# Adafruit_2_13in_Tri-Color_eInk_Display.net
KiCad netlist of a schematic drawn in EAGLE
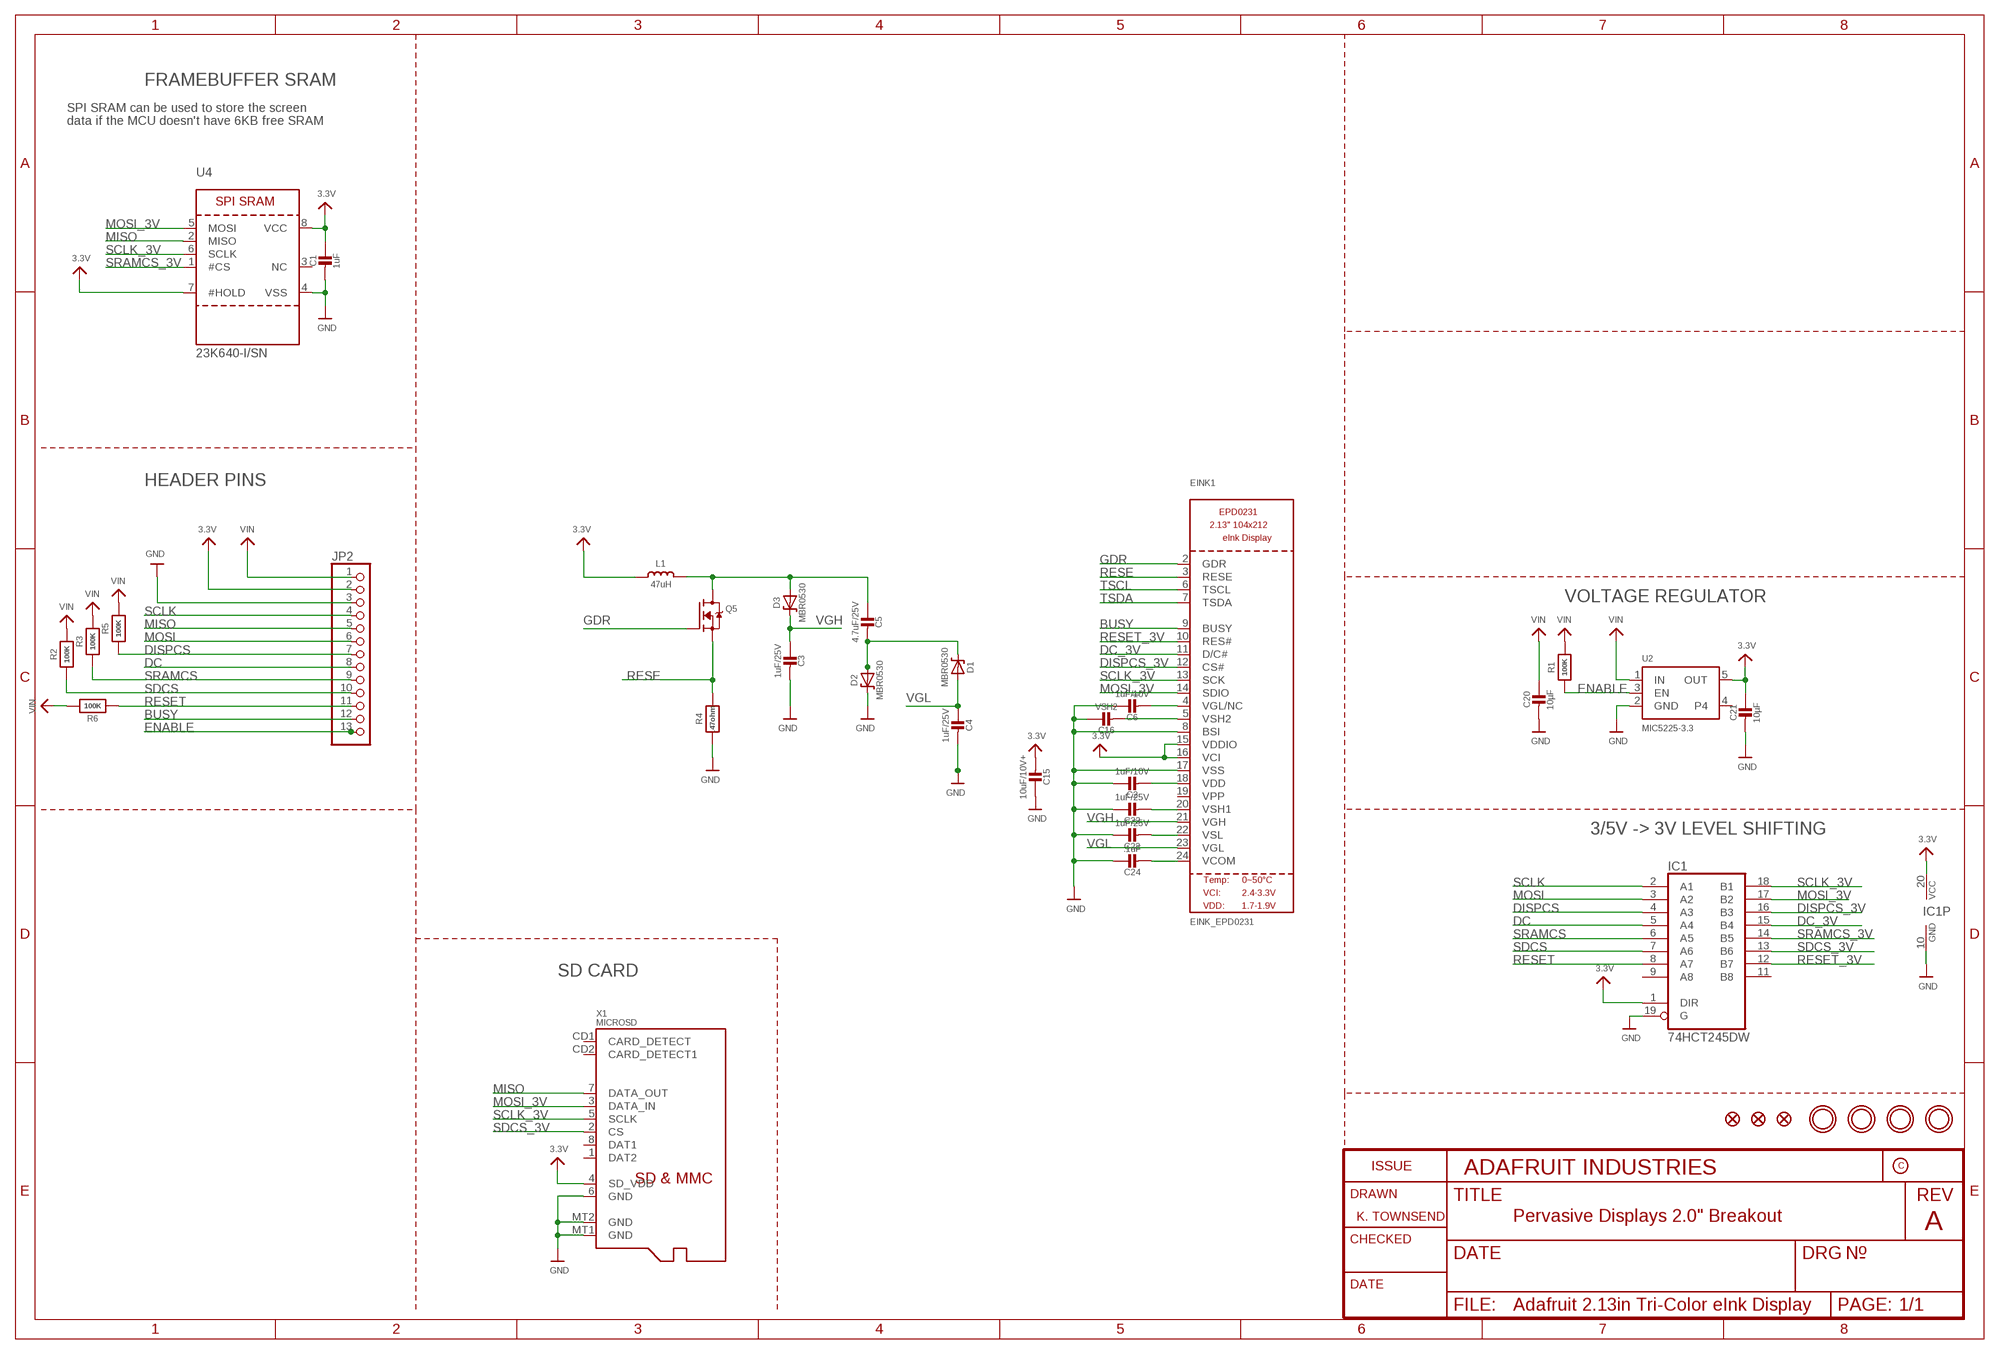
[diagram p0: schematic, sheet 1]

(export (version "E")
  (design (tool "Eeschema 10.0.6"))
  (components
    (comp (ref "C1")
      (value "1uF")
      (footprint "eagle-import:0805_10MGAP")
      (libsource (lib "eagle-import") (part "CAP_CERAMIC0805_10MGAP"))
    )
    (comp (ref "C2")
      (value "1uF/10V")
      (footprint "eagle-import:0805-NO")
      (libsource (lib "eagle-import") (part "CAP_CERAMIC0805-NOOUTLINE"))
    )
    (comp (ref "C3")
      (value "1uF/25V")
      (footprint "eagle-import:0805-NO")
      (libsource (lib "eagle-import") (part "CAP_CERAMIC0805-NOOUTLINE"))
    )
    (comp (ref "C4")
      (value "1uF/25V")
      (footprint "eagle-import:0805-NO")
      (libsource (lib "eagle-import") (part "CAP_CERAMIC0805-NOOUTLINE"))
    )
    (comp (ref "C5")
      (value "4.7uF/25V")
      (footprint "eagle-import:0805-NO")
      (libsource (lib "eagle-import") (part "CAP_CERAMIC0805-NOOUTLINE"))
    )
    (comp (ref "C6")
      (value "1uF/10V")
      (footprint "eagle-import:0805-NO")
      (libsource (lib "eagle-import") (part "CAP_CERAMIC0805-NOOUTLINE"))
    )
    (comp (ref "C15")
      (value "10uF/10V+")
      (footprint "eagle-import:0805-NO")
      (libsource (lib "eagle-import") (part "CAP_CERAMIC0805-NOOUTLINE"))
    )
    (comp (ref "C16")
      (value "VSH2")
      (footprint "eagle-import:0805-NO")
      (libsource (lib "eagle-import") (part "CAP_CERAMIC0805-NOOUTLINE"))
    )
    (comp (ref "C20")
      (value "10µF")
      (footprint "eagle-import:0805-NO")
      (libsource (lib "eagle-import") (part "CAP_CERAMIC0805-NOOUTLINE"))
    )
    (comp (ref "C21")
      (value "10µF")
      (footprint "eagle-import:0805-NO")
      (libsource (lib "eagle-import") (part "CAP_CERAMIC0805-NOOUTLINE"))
    )
    (comp (ref "C22")
      (value "1uF/25V")
      (footprint "eagle-import:0805-NO")
      (libsource (lib "eagle-import") (part "CAP_CERAMIC0805-NOOUTLINE"))
    )
    (comp (ref "C23")
      (value "1uF/25V")
      (footprint "eagle-import:0805-NO")
      (libsource (lib "eagle-import") (part "CAP_CERAMIC0805-NOOUTLINE"))
    )
    (comp (ref "C24")
      (value ".1uF")
      (footprint "eagle-import:0805-NO")
      (libsource (lib "eagle-import") (part "CAP_CERAMIC0805-NOOUTLINE"))
    )
    (comp (ref "D1")
      (value "MBR0530")
      (footprint "eagle-import:SOD-123")
      (libsource (lib "eagle-import") (part "DIODE-SCHOTTKYSOD-123"))
    )
    (comp (ref "D2")
      (value "MBR0530")
      (footprint "eagle-import:SOD-123")
      (libsource (lib "eagle-import") (part "DIODE-SCHOTTKYSOD-123"))
    )
    (comp (ref "D3")
      (value "MBR0530")
      (footprint "eagle-import:SOD-123")
      (libsource (lib "eagle-import") (part "DIODE-SCHOTTKYSOD-123"))
    )
    (comp (ref "EINK1")
      (value "EINK_EPD0231")
      (footprint "eagle-import:EINK_213IN_104X212")
      (libsource (lib "eagle-import") (part "EINK_EPD0231"))
    )
    (comp (ref "FID1")
      (value "FIDUCIAL_1MM")
      (footprint "eagle-import:FIDUCIAL_1MM")
      (libsource (lib "eagle-import") (part "FIDUCIAL_1MM"))
    )
    (comp (ref "FID2")
      (value "FIDUCIAL_1MM")
      (footprint "eagle-import:FIDUCIAL_1MM")
      (libsource (lib "eagle-import") (part "FIDUCIAL_1MM"))
    )
    (comp (ref "FID3")
      (value "FIDUCIAL_1MM")
      (footprint "eagle-import:FIDUCIAL_1MM")
      (libsource (lib "eagle-import") (part "FIDUCIAL_1MM"))
    )
    (comp (ref "IC1")
      (value "74HCT245DW")
      (footprint "eagle-import:SO20W")
      (libsource (lib "eagle-import") (part "74245DWHCT"))
    )
    (comp (ref "JP2")
      (value "HEADER-1X13")
      (footprint "eagle-import:1X13_ROUND_70")
      (libsource (lib "eagle-import") (part "HEADER-1X13"))
    )
    (comp (ref "L1")
      (value "47uH")
      (footprint "eagle-import:INDUCTOR_4X4MM_NR401")
      (libsource (lib "eagle-import") (part "INDUCTORNR401"))
    )
    (comp (ref "Q5")
      (value "IRLML0100")
      (footprint "eagle-import:SOT23-3")
      (libsource (lib "eagle-import") (part "IRLML2060TRPBF"))
    )
    (comp (ref "R1")
      (value "100K")
      (footprint "eagle-import:0805-NO")
      (libsource (lib "eagle-import") (part "RESISTOR0805_NOOUTLINE"))
    )
    (comp (ref "R2")
      (value "100K")
      (footprint "eagle-import:0805-NO")
      (libsource (lib "eagle-import") (part "RESISTOR0805_NOOUTLINE"))
    )
    (comp (ref "R3")
      (value "100K")
      (footprint "eagle-import:0805-NO")
      (libsource (lib "eagle-import") (part "RESISTOR0805_NOOUTLINE"))
    )
    (comp (ref "R4")
      (value ".47ohm")
      (footprint "eagle-import:0805_10MGAP")
      (libsource (lib "eagle-import") (part "RESISTOR0805_10MGAP"))
    )
    (comp (ref "R5")
      (value "100K")
      (footprint "eagle-import:0805-NO")
      (libsource (lib "eagle-import") (part "RESISTOR0805_NOOUTLINE"))
    )
    (comp (ref "R6")
      (value "100K")
      (footprint "eagle-import:0805-NO")
      (libsource (lib "eagle-import") (part "RESISTOR0805_NOOUTLINE"))
    )
    (comp (ref "U$3")
      (value "MOUNTINGHOLE2.5")
      (footprint "eagle-import:MOUNTINGHOLE_2.5_PLATED")
      (libsource (lib "eagle-import") (part "MOUNTINGHOLE2.5"))
    )
    (comp (ref "U$4")
      (value "MOUNTINGHOLE2.5")
      (footprint "eagle-import:MOUNTINGHOLE_2.5_PLATED")
      (libsource (lib "eagle-import") (part "MOUNTINGHOLE2.5"))
    )
    (comp (ref "U$5")
      (value "MOUNTINGHOLE2.5")
      (footprint "eagle-import:MOUNTINGHOLE_2.5_PLATED")
      (libsource (lib "eagle-import") (part "MOUNTINGHOLE2.5"))
    )
    (comp (ref "U$6")
      (value "MOUNTINGHOLE2.5")
      (footprint "eagle-import:MOUNTINGHOLE_2.5_PLATED")
      (libsource (lib "eagle-import") (part "MOUNTINGHOLE2.5"))
    )
    (comp (ref "U2")
      (value "MIC5225-3.3")
      (footprint "eagle-import:SOT23-5")
      (libsource (lib "eagle-import") (part "VREG_SOT23-5"))
    )
    (comp (ref "U4")
      (value "23K640-I/SN")
      (footprint "eagle-import:SOIC8_150MIL")
      (libsource (lib "eagle-import") (part "SRAM_SPI_SOIC8"))
    )
    (comp (ref "X1")
      (value "MICROSD")
      (footprint "eagle-import:MICROSD")
      (libsource (lib "eagle-import") (part "MICROSD"))
    )
  )
  (nets
    (net (code "1") (name "/BUSY") (class "Default")
      (node (ref "EINK1") (pin "9") (pinfunction "BUSY_9") (pintype "output"))
      (node (ref "JP2") (pin "12") (pinfunction "12_12") (pintype "passive"))
    )
    (net (code "2") (name "/DC") (class "Default")
      (node (ref "IC1") (pin "5") (pinfunction "A4_5") (pintype "bidirectional"))
      (node (ref "JP2") (pin "8") (pinfunction "8_8") (pintype "passive"))
    )
    (net (code "3") (name "/DC_3V") (class "Default")
      (node (ref "EINK1") (pin "11") (pinfunction "D/C#_11") (pintype "input"))
      (node (ref "IC1") (pin "15") (pinfunction "B4_15") (pintype "bidirectional"))
    )
    (net (code "4") (name "/DISPCS") (class "Default")
      (node (ref "IC1") (pin "4") (pinfunction "A3_4") (pintype "bidirectional"))
      (node (ref "JP2") (pin "7") (pinfunction "7_7") (pintype "passive"))
      (node (ref "R5") (pin "1") (pinfunction "1_1") (pintype "passive"))
    )
    (net (code "5") (name "/DISPCS_3V") (class "Default")
      (node (ref "EINK1") (pin "12") (pinfunction "CS#_12") (pintype "input"))
      (node (ref "IC1") (pin "16") (pinfunction "B3_16") (pintype "bidirectional"))
    )
    (net (code "6") (name "/ENABLE") (class "Default")
      (node (ref "JP2") (pin "13") (pinfunction "13_13") (pintype "passive"))
      (node (ref "R1") (pin "1") (pinfunction "1_1") (pintype "passive"))
      (node (ref "U2") (pin "3") (pinfunction "EN_3") (pintype "input"))
    )
    (net (code "7") (name "/GDR") (class "Default")
      (node (ref "EINK1") (pin "2") (pinfunction "GDR_2") (pintype "output"))
      (node (ref "Q5") (pin "1") (pinfunction "G_1") (pintype "bidirectional"))
    )
    (net (code "8") (name "/MISO") (class "Default")
      (node (ref "JP2") (pin "5") (pinfunction "5_5") (pintype "passive"))
      (node (ref "U4") (pin "2") (pinfunction "MISO_2") (pintype "output"))
      (node (ref "X1") (pin "7") (pinfunction "DATA_OUT_7") (pintype "output"))
    )
    (net (code "9") (name "/MOSI") (class "Default")
      (node (ref "IC1") (pin "3") (pinfunction "A2_3") (pintype "bidirectional"))
      (node (ref "JP2") (pin "6") (pinfunction "6_6") (pintype "passive"))
    )
    (net (code "10") (name "/MOSI_3V") (class "Default")
      (node (ref "EINK1") (pin "14") (pinfunction "SDIO_14") (pintype "bidirectional"))
      (node (ref "IC1") (pin "17") (pinfunction "B2_17") (pintype "bidirectional"))
      (node (ref "U4") (pin "5") (pinfunction "MOSI_5") (pintype "input"))
      (node (ref "X1") (pin "3") (pinfunction "DATA_IN_3") (pintype "input"))
    )
    (net (code "11") (name "/RESE") (class "Default")
      (node (ref "EINK1") (pin "3") (pinfunction "RESE_3") (pintype "input"))
      (node (ref "Q5") (pin "2") (pinfunction "S_2") (pintype "bidirectional"))
      (node (ref "R4") (pin "1") (pinfunction "1_1") (pintype "passive"))
    )
    (net (code "12") (name "/RESET") (class "Default")
      (node (ref "IC1") (pin "8") (pinfunction "A7_8") (pintype "bidirectional"))
      (node (ref "JP2") (pin "11") (pinfunction "11_11") (pintype "passive"))
      (node (ref "R6") (pin "1") (pinfunction "1_1") (pintype "passive"))
    )
    (net (code "13") (name "/RESET_3V") (class "Default")
      (node (ref "EINK1") (pin "10") (pinfunction "RES#_10") (pintype "input"))
      (node (ref "IC1") (pin "12") (pinfunction "B7_12") (pintype "bidirectional"))
    )
    (net (code "14") (name "/SCLK") (class "Default")
      (node (ref "IC1") (pin "2") (pinfunction "A1_2") (pintype "bidirectional"))
      (node (ref "JP2") (pin "4") (pinfunction "4_4") (pintype "passive"))
    )
    (net (code "15") (name "/SCLK_3V") (class "Default")
      (node (ref "EINK1") (pin "13") (pinfunction "SCK_13") (pintype "bidirectional"))
      (node (ref "IC1") (pin "18") (pinfunction "B1_18") (pintype "bidirectional"))
      (node (ref "U4") (pin "6") (pinfunction "SCLK_6") (pintype "input"))
      (node (ref "X1") (pin "5") (pinfunction "SCLK_5") (pintype "input"))
    )
    (net (code "16") (name "/SDCS") (class "Default")
      (node (ref "IC1") (pin "7") (pinfunction "A6_7") (pintype "bidirectional"))
      (node (ref "JP2") (pin "10") (pinfunction "10_10") (pintype "passive"))
      (node (ref "R2") (pin "1") (pinfunction "1_1") (pintype "passive"))
    )
    (net (code "17") (name "/SDCS_3V") (class "Default")
      (node (ref "IC1") (pin "13") (pinfunction "B6_13") (pintype "bidirectional"))
      (node (ref "X1") (pin "2") (pinfunction "CS_2") (pintype "input"))
    )
    (net (code "18") (name "/SRAMCS") (class "Default")
      (node (ref "IC1") (pin "6") (pinfunction "A5_6") (pintype "bidirectional"))
      (node (ref "JP2") (pin "9") (pinfunction "9_9") (pintype "passive"))
      (node (ref "R3") (pin "1") (pinfunction "1_1") (pintype "passive"))
    )
    (net (code "19") (name "/SRAMCS_3V") (class "Default")
      (node (ref "IC1") (pin "14") (pinfunction "B5_14") (pintype "bidirectional"))
      (node (ref "U4") (pin "1") (pinfunction "#CS_1") (pintype "input"))
    )
    (net (code "20") (name "/TSCL") (class "Default")
      (node (ref "EINK1") (pin "6") (pinfunction "TSCL_6") (pintype "output"))
    )
    (net (code "21") (name "/TSDA") (class "Default")
      (node (ref "EINK1") (pin "7") (pinfunction "TSDA_7") (pintype "bidirectional"))
    )
    (net (code "22") (name "/VGH") (class "Default")
      (node (ref "C3") (pin "1") (pinfunction "1_1") (pintype "passive"))
      (node (ref "D3") (pin "C") (pinfunction "C_C") (pintype "passive"))
      (node (ref "EINK1") (pin "21") (pinfunction "VGH_21") (pintype "passive"))
    )
    (net (code "23") (name "/VGL") (class "Default")
      (node (ref "C4") (pin "1") (pinfunction "1_1") (pintype "passive"))
      (node (ref "D1") (pin "A") (pinfunction "A_A") (pintype "passive"))
      (node (ref "EINK1") (pin "23") (pinfunction "VGL_23") (pintype "passive"))
    )
    (net (code "24") (name "3.3V") (class "Default")
      (node (ref "C1") (pin "1") (pinfunction "1_1") (pintype "passive"))
      (node (ref "C15") (pin "2") (pinfunction "2_2") (pintype "passive"))
      (node (ref "C21") (pin "1") (pinfunction "1_1") (pintype "passive"))
      (node (ref "EINK1") (pin "15") (pinfunction "VDDIO_15") (pintype "power_in"))
      (node (ref "EINK1") (pin "16") (pinfunction "VCI_16") (pintype "power_in"))
      (node (ref "IC1") (pin "1") (pinfunction "DIR_1") (pintype "input"))
      (node (ref "IC1") (pin "20") (pinfunction "VCC_20") (pintype "power_in"))
      (node (ref "JP2") (pin "2") (pinfunction "2_2") (pintype "passive"))
      (node (ref "L1") (pin "P$2") (pinfunction "2_P$2") (pintype "passive"))
      (node (ref "U2") (pin "5") (pinfunction "OUT_5") (pintype "power_in"))
      (node (ref "U4") (pin "7") (pinfunction "#HOLD_7") (pintype "input"))
      (node (ref "U4") (pin "8") (pinfunction "VCC_8") (pintype "power_in"))
      (node (ref "X1") (pin "4") (pinfunction "SD_VDD_4") (pintype "power_in"))
    )
    (net (code "25") (name "GND") (class "Default")
      (node (ref "C1") (pin "2") (pinfunction "2_2") (pintype "passive"))
      (node (ref "C15") (pin "1") (pinfunction "1_1") (pintype "passive"))
      (node (ref "C16") (pin "1") (pinfunction "1_1") (pintype "passive"))
      (node (ref "C2") (pin "1") (pinfunction "1_1") (pintype "passive"))
      (node (ref "C20") (pin "2") (pinfunction "2_2") (pintype "passive"))
      (node (ref "C21") (pin "2") (pinfunction "2_2") (pintype "passive"))
      (node (ref "C22") (pin "1") (pinfunction "1_1") (pintype "passive"))
      (node (ref "C23") (pin "1") (pinfunction "1_1") (pintype "passive"))
      (node (ref "C24") (pin "1") (pinfunction "1_1") (pintype "passive"))
      (node (ref "C3") (pin "2") (pinfunction "2_2") (pintype "passive"))
      (node (ref "C4") (pin "2") (pinfunction "2_2") (pintype "passive"))
      (node (ref "C6") (pin "1") (pinfunction "1_1") (pintype "passive"))
      (node (ref "D2") (pin "C") (pinfunction "C_C") (pintype "passive"))
      (node (ref "EINK1") (pin "17") (pinfunction "VSS_17") (pintype "power_in"))
      (node (ref "EINK1") (pin "8") (pinfunction "BSI_8") (pintype "input"))
      (node (ref "IC1") (pin "10") (pinfunction "GND_10") (pintype "power_in"))
      (node (ref "IC1") (pin "19") (pinfunction "G_19") (pintype "input"))
      (node (ref "JP2") (pin "3") (pinfunction "3_3") (pintype "passive"))
      (node (ref "R4") (pin "2") (pinfunction "2_2") (pintype "passive"))
      (node (ref "U2") (pin "2") (pinfunction "GND_2") (pintype "power_in"))
      (node (ref "U4") (pin "4") (pinfunction "VSS_4") (pintype "power_in"))
      (node (ref "X1") (pin "6") (pinfunction "GND_6") (pintype "power_in"))
      (node (ref "X1") (pin "MT1") (pinfunction "GND_MT1") (pintype "power_in"))
      (node (ref "X1") (pin "MT2") (pinfunction "GND_MT2") (pintype "power_in"))
    )
    (net (code "26") (name "Net-(C5-Pad2)") (class "Default")
      (node (ref "C5") (pin "2") (pinfunction "2_2") (pintype "passive"))
      (node (ref "D1") (pin "C") (pinfunction "C_C") (pintype "passive"))
      (node (ref "D2") (pin "A") (pinfunction "A_A") (pintype "passive"))
    )
    (net (code "27") (name "Net-(EINK1-VCOM)") (class "Default")
      (node (ref "C24") (pin "2") (pinfunction "2_2") (pintype "passive"))
      (node (ref "EINK1") (pin "24") (pinfunction "VCOM_24") (pintype "passive"))
    )
    (net (code "28") (name "Net-(EINK1-VDD)") (class "Default")
      (node (ref "C2") (pin "2") (pinfunction "2_2") (pintype "passive"))
      (node (ref "EINK1") (pin "18") (pinfunction "VDD_18") (pintype "passive"))
    )
    (net (code "29") (name "Net-(EINK1-VGL{slash}NC)") (class "Default")
      (node (ref "C6") (pin "2") (pinfunction "2_2") (pintype "passive"))
      (node (ref "EINK1") (pin "4") (pinfunction "VGL/NC_4") (pintype "bidirectional"))
    )
    (net (code "30") (name "Net-(EINK1-VSH1)") (class "Default")
      (node (ref "C22") (pin "2") (pinfunction "2_2") (pintype "passive"))
      (node (ref "EINK1") (pin "20") (pinfunction "VSH1_20") (pintype "passive"))
    )
    (net (code "31") (name "Net-(EINK1-VSH2)") (class "Default")
      (node (ref "C16") (pin "2") (pinfunction "2_2") (pintype "passive"))
      (node (ref "EINK1") (pin "5") (pinfunction "VSH2_5") (pintype "passive"))
    )
    (net (code "32") (name "Net-(EINK1-VSL)") (class "Default")
      (node (ref "C23") (pin "2") (pinfunction "2_2") (pintype "passive"))
      (node (ref "EINK1") (pin "22") (pinfunction "VSL_22") (pintype "passive"))
    )
    (net (code "33") (name "Net-(L1-1)") (class "Default")
      (node (ref "C5") (pin "1") (pinfunction "1_1") (pintype "passive"))
      (node (ref "D3") (pin "A") (pinfunction "A_A") (pintype "passive"))
      (node (ref "L1") (pin "P$1") (pinfunction "1_P$1") (pintype "passive"))
      (node (ref "Q5") (pin "3") (pinfunction "D_3") (pintype "bidirectional"))
    )
    (net (code "34") (name "VIN") (class "Default")
      (node (ref "C20") (pin "1") (pinfunction "1_1") (pintype "passive"))
      (node (ref "JP2") (pin "1") (pinfunction "1_1") (pintype "passive"))
      (node (ref "R1") (pin "2") (pinfunction "2_2") (pintype "passive"))
      (node (ref "R2") (pin "2") (pinfunction "2_2") (pintype "passive"))
      (node (ref "R3") (pin "2") (pinfunction "2_2") (pintype "passive"))
      (node (ref "R5") (pin "2") (pinfunction "2_2") (pintype "passive"))
      (node (ref "R6") (pin "2") (pinfunction "2_2") (pintype "passive"))
      (node (ref "U2") (pin "1") (pinfunction "IN_1") (pintype "power_in"))
    )
    (net (code "35") (name "unconnected-(EINK1-VPP-Pad19)") (class "Default")
      (node (ref "EINK1") (pin "19") (pinfunction "VPP_19") (pintype "passive"))
    )
    (net (code "36") (name "unconnected-(IC1A-A8-Pad9)") (class "Default")
      (node (ref "IC1") (pin "9") (pinfunction "A8_9") (pintype "bidirectional"))
    )
    (net (code "37") (name "unconnected-(IC1A-B8-Pad11)") (class "Default")
      (node (ref "IC1") (pin "11") (pinfunction "B8_11") (pintype "bidirectional"))
    )
    (net (code "38") (name "unconnected-(U2-P4-Pad4)") (class "Default")
      (node (ref "U2") (pin "4") (pinfunction "P4_4") (pintype "bidirectional"))
    )
    (net (code "39") (name "unconnected-(U4-NC-Pad3)") (class "Default")
      (node (ref "U4") (pin "3") (pinfunction "NC_3") (pintype "no_connect"))
    )
    (net (code "40") (name "unconnected-(X1-CARD_DETECT-PadCD1)") (class "Default")
      (node (ref "X1") (pin "CD1") (pinfunction "CARD_DETECT_CD1") (pintype "passive"))
    )
    (net (code "41") (name "unconnected-(X1-CARD_DETECT1-PadCD2)") (class "Default")
      (node (ref "X1") (pin "CD2") (pinfunction "CARD_DETECT1_CD2") (pintype "passive"))
    )
    (net (code "42") (name "unconnected-(X1-DAT1-Pad8)") (class "Default")
      (node (ref "X1") (pin "8") (pinfunction "DAT1_8") (pintype "bidirectional"))
    )
    (net (code "43") (name "unconnected-(X1-DAT2-Pad1)") (class "Default")
      (node (ref "X1") (pin "1") (pinfunction "DAT2_1") (pintype "bidirectional"))
    )
  )
)
